# DIY_DAP_PCB_PIC32.net
KiCad netlist of a schematic drawn in Altium Designer
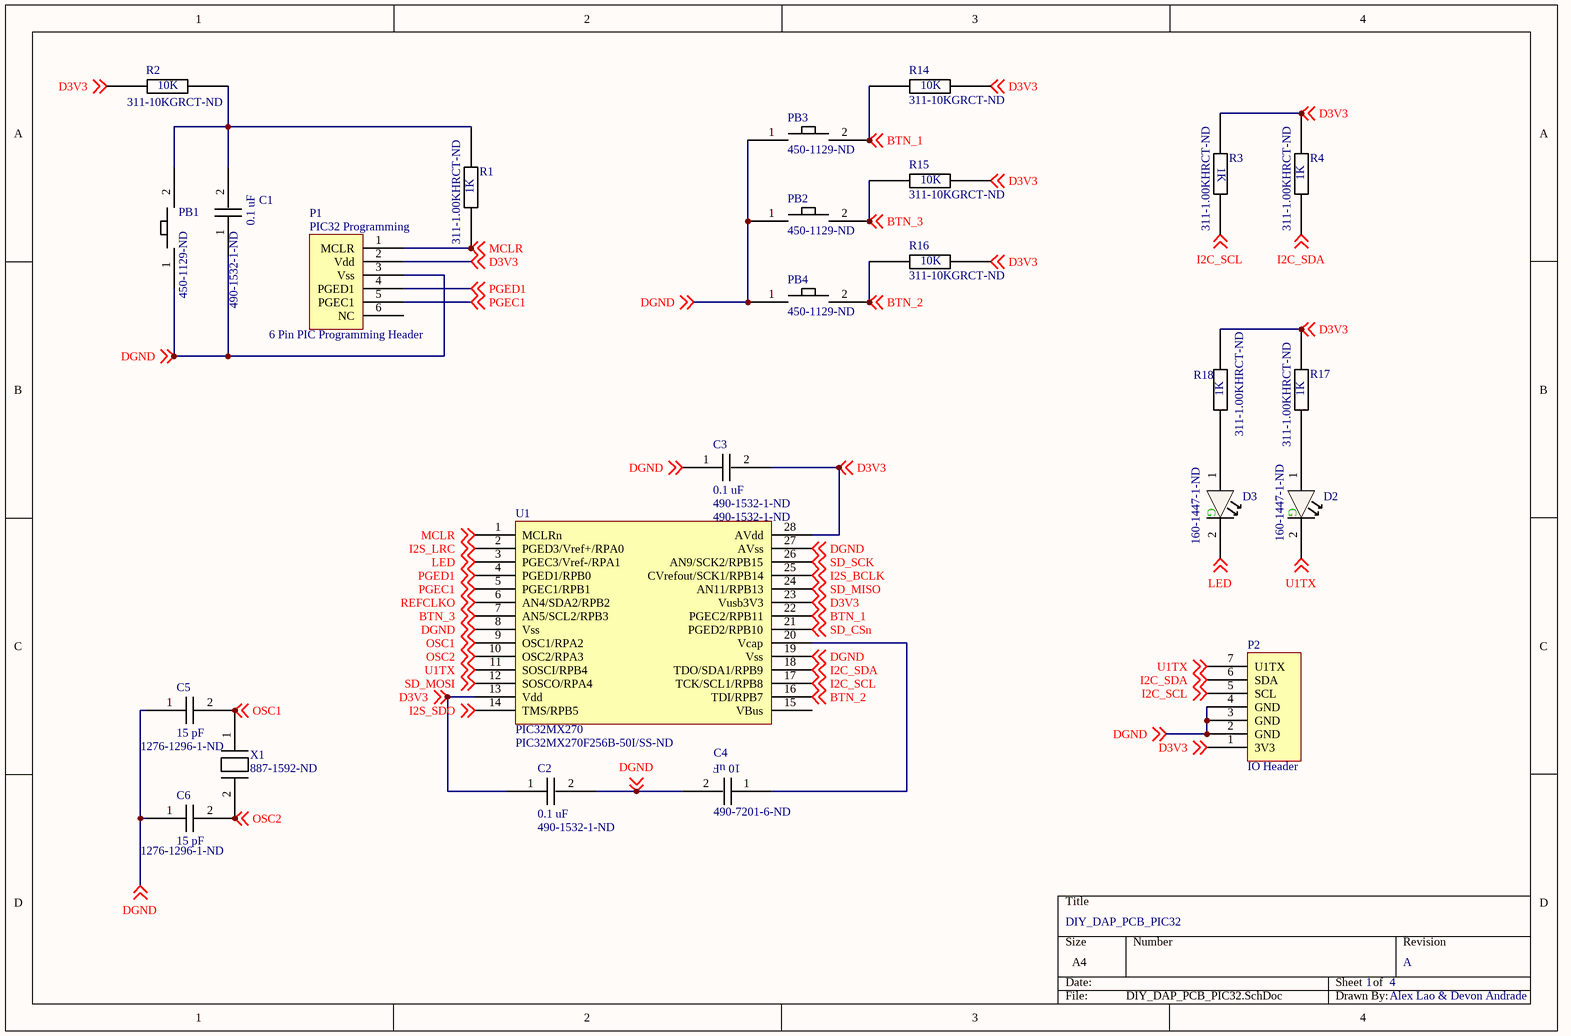
[diagram p0: DIY_DAP_PCB_PIC32.SchDoc]

(export (version "E")
  (design (tool "Eeschema 10.0.6"))
  (components
    (comp (ref "C1")
      (value "490-1532-1-ND")
      (footprint "0603")
      (description "0603 0.1 uF - 16V - Ceramic Capacitor")
      (libsource (lib "DIY_DAP_PCB_Library") (part "490-1532-1-ND"))
    )
    (comp (ref "C2")
      (value "490-1532-1-ND")
      (footprint "0603")
      (description "0603 0.1 uF - 16V - Ceramic Capacitor")
      (libsource (lib "DIY_DAP_PCB_Library") (part "490-1532-1-ND"))
    )
    (comp (ref "C3")
      (value "490-1532-1-ND")
      (footprint "0603")
      (description "0603 0.1 uF - 16V - Ceramic Capacitor")
      (fields (field (name "SUPPLIER PART NUMBER 1") "490-1532-1-ND"))
      (libsource (lib "DIY_DAP_PCB_Library") (part "490-1532-1-ND"))
    )
    (comp (ref "C4")
      (value "490-7201-6-ND")
      (footprint "0603")
      (description "0603 10 uF - 16V - Ceramic Capacitor")
      (libsource (lib "DIY_DAP_PCB_Library") (part "490-7201-6-ND"))
    )
    (comp (ref "C5")
      (value "1276-1296-1-ND")
      (footprint "0603")
      (description "0603 15 pF - 50V - Ceramic Capacitor")
      (libsource (lib "DIY_DAP_PCB_Library") (part "1276-1296-1-ND"))
    )
    (comp (ref "C6")
      (value "1276-1296-1-ND")
      (footprint "0603")
      (description "0603 15 pF - 50V - Ceramic Capacitor")
      (libsource (lib "DIY_DAP_PCB_Library") (part "1276-1296-1-ND"))
    )
    (comp (ref "D2")
      (value "160-1447-1-ND")
      (footprint "0603")
      (description "Green LED (0603)")
      (libsource (lib "DIY_DAP_PCB_Library") (part "160-1447-1-ND"))
    )
    (comp (ref "D3")
      (value "160-1447-1-ND")
      (footprint "0603")
      (description "Green LED (0603)")
      (libsource (lib "DIY_DAP_PCB_Library") (part "160-1447-1-ND"))
    )
    (comp (ref "P1")
      (value "6 Pin PIC Programming Header")
      (footprint "PIC32 Programming Header")
      (libsource (lib "DIY_DAP_PCB_Library") (part "6 Pin PIC Programming Header"))
    )
    (comp (ref "P2")
      (value "IO Header")
      (footprint "IO Header")
      (libsource (lib "DIY_DAP_PCB_Library") (part "IO Header"))
    )
    (comp (ref "PB1")
      (value "450-1129-ND")
      (footprint "450-1129-ND")
      (description "Momentary Push button")
      (libsource (lib "DIY_DAP_PCB_Library") (part "450-1129-ND"))
    )
    (comp (ref "PB2")
      (value "450-1129-ND")
      (footprint "450-1129-ND")
      (description "Momentary Push button")
      (libsource (lib "DIY_DAP_PCB_Library") (part "450-1129-ND"))
    )
    (comp (ref "PB3")
      (value "450-1129-ND")
      (footprint "450-1129-ND")
      (description "Momentary Push button")
      (libsource (lib "DIY_DAP_PCB_Library") (part "450-1129-ND"))
    )
    (comp (ref "PB4")
      (value "450-1129-ND")
      (footprint "450-1129-ND")
      (description "Momentary Push button")
      (libsource (lib "DIY_DAP_PCB_Library") (part "450-1129-ND"))
    )
    (comp (ref "R1")
      (value "311-1.00KHRCT-ND")
      (footprint "0603")
      (description "1k Ohm Resistor")
      (libsource (lib "DIY_DAP_PCB_Library") (part "311-1.00KHRCT-ND"))
    )
    (comp (ref "R2")
      (value "311-10KGRCT-ND")
      (footprint "0603")
      (description "10k Ohm Resistor")
      (libsource (lib "DIY_DAP_PCB_Library") (part "311-10KGRCT-ND"))
    )
    (comp (ref "R3")
      (value "311-1.00KHRCT-ND")
      (footprint "0603")
      (description "1k Ohm Resistor")
      (libsource (lib "DIY_DAP_PCB_Library") (part "311-1.00KHRCT-ND"))
    )
    (comp (ref "R4")
      (value "311-1.00KHRCT-ND")
      (footprint "0603")
      (description "1k Ohm Resistor")
      (libsource (lib "DIY_DAP_PCB_Library") (part "311-1.00KHRCT-ND"))
    )
    (comp (ref "R14")
      (value "311-10KGRCT-ND")
      (footprint "0603")
      (description "10k Ohm Resistor")
      (libsource (lib "DIY_DAP_PCB_Library") (part "311-10KGRCT-ND"))
    )
    (comp (ref "R15")
      (value "311-10KGRCT-ND")
      (footprint "0603")
      (description "10k Ohm Resistor")
      (libsource (lib "DIY_DAP_PCB_Library") (part "311-10KGRCT-ND"))
    )
    (comp (ref "R16")
      (value "311-10KGRCT-ND")
      (footprint "0603")
      (description "10k Ohm Resistor")
      (libsource (lib "DIY_DAP_PCB_Library") (part "311-10KGRCT-ND"))
    )
    (comp (ref "R17")
      (value "311-1.00KHRCT-ND")
      (footprint "0603")
      (description "1k Ohm Resistor")
      (libsource (lib "DIY_DAP_PCB_Library") (part "311-1.00KHRCT-ND"))
    )
    (comp (ref "R18")
      (value "311-1.00KHRCT-ND")
      (footprint "0603")
      (description "1k Ohm Resistor")
      (libsource (lib "DIY_DAP_PCB_Library") (part "311-1.00KHRCT-ND"))
    )
    (comp (ref "U1")
      (value "PIC32MX270")
      (footprint "PIC32MX270F256B-50I/SS-ND")
      (description "PIC32MX270F256B")
      (fields (field (name "SUPPLIER PART NUMBER 1") "PIC32MX270F256B-50I/SS-ND"))
      (libsource (lib "DIY_DAP_PCB_Library") (part "PIC32MX270F256B-50I/SS-ND"))
    )
    (comp (ref "X1")
      (value "887-1592-ND")
      (footprint "887-1592-ND")
      (description "16.9344 Mhz Crystal")
      (libsource (lib "DIY_DAP_PCB_Library") (part "887-1592-ND"))
    )
  )
  (nets
    (net (code "1") (name "BTN_1") (class "Default")
      (node (ref "PB3") (pin "2") (pinfunction "2_2") (pintype "passive"))
      (node (ref "R14") (pin "1") (pinfunction "1_1") (pintype "passive"))
      (node (ref "U1") (pin "22") (pinfunction "PGEC2/RPB11_22") (pintype "passive"))
    )
    (net (code "2") (name "BTN_2") (class "Default")
      (node (ref "PB4") (pin "2") (pinfunction "2_2") (pintype "passive"))
      (node (ref "R16") (pin "1") (pinfunction "1_1") (pintype "passive"))
      (node (ref "U1") (pin "16") (pinfunction "TDI/RPB7_16") (pintype "passive"))
    )
    (net (code "3") (name "BTN_3") (class "Default")
      (node (ref "PB2") (pin "2") (pinfunction "2_2") (pintype "passive"))
      (node (ref "R15") (pin "1") (pinfunction "1_1") (pintype "passive"))
      (node (ref "U1") (pin "7") (pinfunction "AN5/SCL2/RPB3_7") (pintype "passive"))
    )
    (net (code "4") (name "D3V3") (class "Default")
      (node (ref "C2") (pin "1") (pinfunction "1_1") (pintype "passive"))
      (node (ref "C3") (pin "2") (pinfunction "2_2") (pintype "passive"))
      (node (ref "P1") (pin "2") (pinfunction "Vdd_2") (pintype "passive"))
      (node (ref "P2") (pin "1") (pinfunction "3V3_1") (pintype "passive"))
      (node (ref "R14") (pin "2") (pinfunction "2_2") (pintype "passive"))
      (node (ref "R15") (pin "2") (pinfunction "2_2") (pintype "passive"))
      (node (ref "R16") (pin "2") (pinfunction "2_2") (pintype "passive"))
      (node (ref "R17") (pin "2") (pinfunction "2_2") (pintype "passive"))
      (node (ref "R18") (pin "2") (pinfunction "2_2") (pintype "passive"))
      (node (ref "R2") (pin "1") (pinfunction "1_1") (pintype "passive"))
      (node (ref "R3") (pin "1") (pinfunction "1_1") (pintype "passive"))
      (node (ref "R4") (pin "2") (pinfunction "2_2") (pintype "passive"))
      (node (ref "U1") (pin "13") (pinfunction "Vdd_13") (pintype "passive"))
      (node (ref "U1") (pin "23") (pinfunction "Vusb3V3_23") (pintype "passive"))
      (node (ref "U1") (pin "28") (pinfunction "AVdd_28") (pintype "passive"))
    )
    (net (code "5") (name "DGND") (class "Default")
      (node (ref "C1") (pin "1") (pinfunction "1_1") (pintype "passive"))
      (node (ref "C2") (pin "2") (pinfunction "2_2") (pintype "passive"))
      (node (ref "C3") (pin "1") (pinfunction "1_1") (pintype "passive"))
      (node (ref "C4") (pin "2") (pinfunction "2_2") (pintype "passive"))
      (node (ref "C5") (pin "1") (pinfunction "1_1") (pintype "passive"))
      (node (ref "C6") (pin "1") (pinfunction "1_1") (pintype "passive"))
      (node (ref "P1") (pin "3") (pinfunction "Vss_3") (pintype "passive"))
      (node (ref "P2") (pin "2") (pinfunction "GND_2") (pintype "passive"))
      (node (ref "P2") (pin "3") (pinfunction "GND_3") (pintype "passive"))
      (node (ref "P2") (pin "4") (pinfunction "GND_4") (pintype "passive"))
      (node (ref "PB1") (pin "1") (pinfunction "1_1") (pintype "passive"))
      (node (ref "PB2") (pin "1") (pinfunction "1_1") (pintype "passive"))
      (node (ref "PB3") (pin "1") (pinfunction "1_1") (pintype "passive"))
      (node (ref "PB4") (pin "1") (pinfunction "1_1") (pintype "passive"))
      (node (ref "U1") (pin "19") (pinfunction "Vss_19") (pintype "passive"))
      (node (ref "U1") (pin "27") (pinfunction "AVss_27") (pintype "passive"))
      (node (ref "U1") (pin "8") (pinfunction "Vss_8") (pintype "passive"))
    )
    (net (code "6") (name "I2C_SCL") (class "Default")
      (node (ref "P2") (pin "5") (pinfunction "SCL_5") (pintype "passive"))
      (node (ref "R3") (pin "2") (pinfunction "2_2") (pintype "passive"))
      (node (ref "U1") (pin "17") (pinfunction "TCK/SCL1/RPB8_17") (pintype "passive"))
    )
    (net (code "7") (name "I2C_SDA") (class "Default")
      (node (ref "P2") (pin "6") (pinfunction "SDA_6") (pintype "passive"))
      (node (ref "R4") (pin "1") (pinfunction "1_1") (pintype "passive"))
      (node (ref "U1") (pin "18") (pinfunction "TDO/SDA1/RPB9_18") (pintype "passive"))
    )
    (net (code "8") (name "I2S_BCLK") (class "Default")
      (node (ref "U1") (pin "25") (pinfunction "CVrefout/SCK1/RPB14_25") (pintype "passive"))
    )
    (net (code "9") (name "I2S_LRC") (class "Default")
      (node (ref "U1") (pin "2") (pinfunction "PGED3/Vref+/RPA0_2") (pintype "passive"))
    )
    (net (code "10") (name "I2S_SDO") (class "Default")
      (node (ref "U1") (pin "14") (pinfunction "TMS/RPB5_14") (pintype "passive"))
    )
    (net (code "11") (name "LED") (class "Default")
      (node (ref "D3") (pin "2") (pinfunction "-_2") (pintype "passive"))
      (node (ref "U1") (pin "3") (pinfunction "PGEC3/Vref-/RPA1_3") (pintype "passive"))
    )
    (net (code "12") (name "MCLR") (class "Default")
      (node (ref "P1") (pin "1") (pinfunction "MCLR_1") (pintype "passive"))
      (node (ref "R1") (pin "1") (pinfunction "1_1") (pintype "passive"))
      (node (ref "U1") (pin "1") (pinfunction "MCLRn_1") (pintype "passive"))
    )
    (net (code "13") (name "Net-(C1-Pad2)") (class "Default")
      (node (ref "C1") (pin "2") (pinfunction "2_2") (pintype "passive"))
      (node (ref "PB1") (pin "2") (pinfunction "2_2") (pintype "passive"))
      (node (ref "R1") (pin "2") (pinfunction "2_2") (pintype "passive"))
      (node (ref "R2") (pin "2") (pinfunction "2_2") (pintype "passive"))
    )
    (net (code "14") (name "Net-(D2-+)") (class "Default")
      (node (ref "D2") (pin "1") (pinfunction "+_1") (pintype "passive"))
      (node (ref "R17") (pin "1") (pinfunction "1_1") (pintype "passive"))
    )
    (net (code "15") (name "Net-(D3-+)") (class "Default")
      (node (ref "D3") (pin "1") (pinfunction "+_1") (pintype "passive"))
      (node (ref "R18") (pin "1") (pinfunction "1_1") (pintype "passive"))
    )
    (net (code "16") (name "Net-(U1-Vcap)") (class "Default")
      (node (ref "C4") (pin "1") (pinfunction "1_1") (pintype "passive"))
      (node (ref "U1") (pin "20") (pinfunction "Vcap_20") (pintype "passive"))
    )
    (net (code "17") (name "OSC1") (class "Default")
      (node (ref "C5") (pin "2") (pinfunction "2_2") (pintype "passive"))
      (node (ref "U1") (pin "9") (pinfunction "OSC1/RPA2_9") (pintype "passive"))
      (node (ref "X1") (pin "1") (pinfunction "1_1") (pintype "passive"))
    )
    (net (code "18") (name "OSC2") (class "Default")
      (node (ref "C6") (pin "2") (pinfunction "2_2") (pintype "passive"))
      (node (ref "U1") (pin "10") (pinfunction "OSC2/RPA3_10") (pintype "passive"))
      (node (ref "X1") (pin "2") (pinfunction "2_2") (pintype "passive"))
    )
    (net (code "19") (name "PGEC1") (class "Default")
      (node (ref "P1") (pin "5") (pinfunction "PGEC1_5") (pintype "passive"))
      (node (ref "U1") (pin "5") (pinfunction "PGEC1/RPB1_5") (pintype "passive"))
    )
    (net (code "20") (name "PGED1") (class "Default")
      (node (ref "P1") (pin "4") (pinfunction "PGED1_4") (pintype "passive"))
      (node (ref "U1") (pin "4") (pinfunction "PGED1/RPB0_4") (pintype "passive"))
    )
    (net (code "21") (name "REFCLKO") (class "Default")
      (node (ref "U1") (pin "6") (pinfunction "AN4/SDA2/RPB2_6") (pintype "passive"))
    )
    (net (code "22") (name "SD_CSn") (class "Default")
      (node (ref "U1") (pin "21") (pinfunction "PGED2/RPB10_21") (pintype "passive"))
    )
    (net (code "23") (name "SD_MISO") (class "Default")
      (node (ref "U1") (pin "24") (pinfunction "AN11/RPB13_24") (pintype "passive"))
    )
    (net (code "24") (name "SD_MOSI") (class "Default")
      (node (ref "U1") (pin "12") (pinfunction "SOSCO/RPA4_12") (pintype "passive"))
    )
    (net (code "25") (name "SD_SCK") (class "Default")
      (node (ref "U1") (pin "26") (pinfunction "AN9/SCK2/RPB15_26") (pintype "passive"))
    )
    (net (code "26") (name "U1TX") (class "Default")
      (node (ref "D2") (pin "2") (pinfunction "-_2") (pintype "passive"))
      (node (ref "P2") (pin "7") (pinfunction "U1TX_7") (pintype "passive"))
      (node (ref "U1") (pin "11") (pinfunction "SOSCI/RPB4_11") (pintype "passive"))
    )
    (net (code "27") (name "unconnected-(P1-NC-Pad6)") (class "Default")
      (node (ref "P1") (pin "6") (pinfunction "NC_6") (pintype "passive"))
    )
    (net (code "28") (name "unconnected-(U1-VBus-Pad15)") (class "Default")
      (node (ref "U1") (pin "15") (pinfunction "VBus_15") (pintype "passive"))
    )
  )
)
